# I2C_Bus.net
KiCad netlist of a schematic drawn in Altium Designer
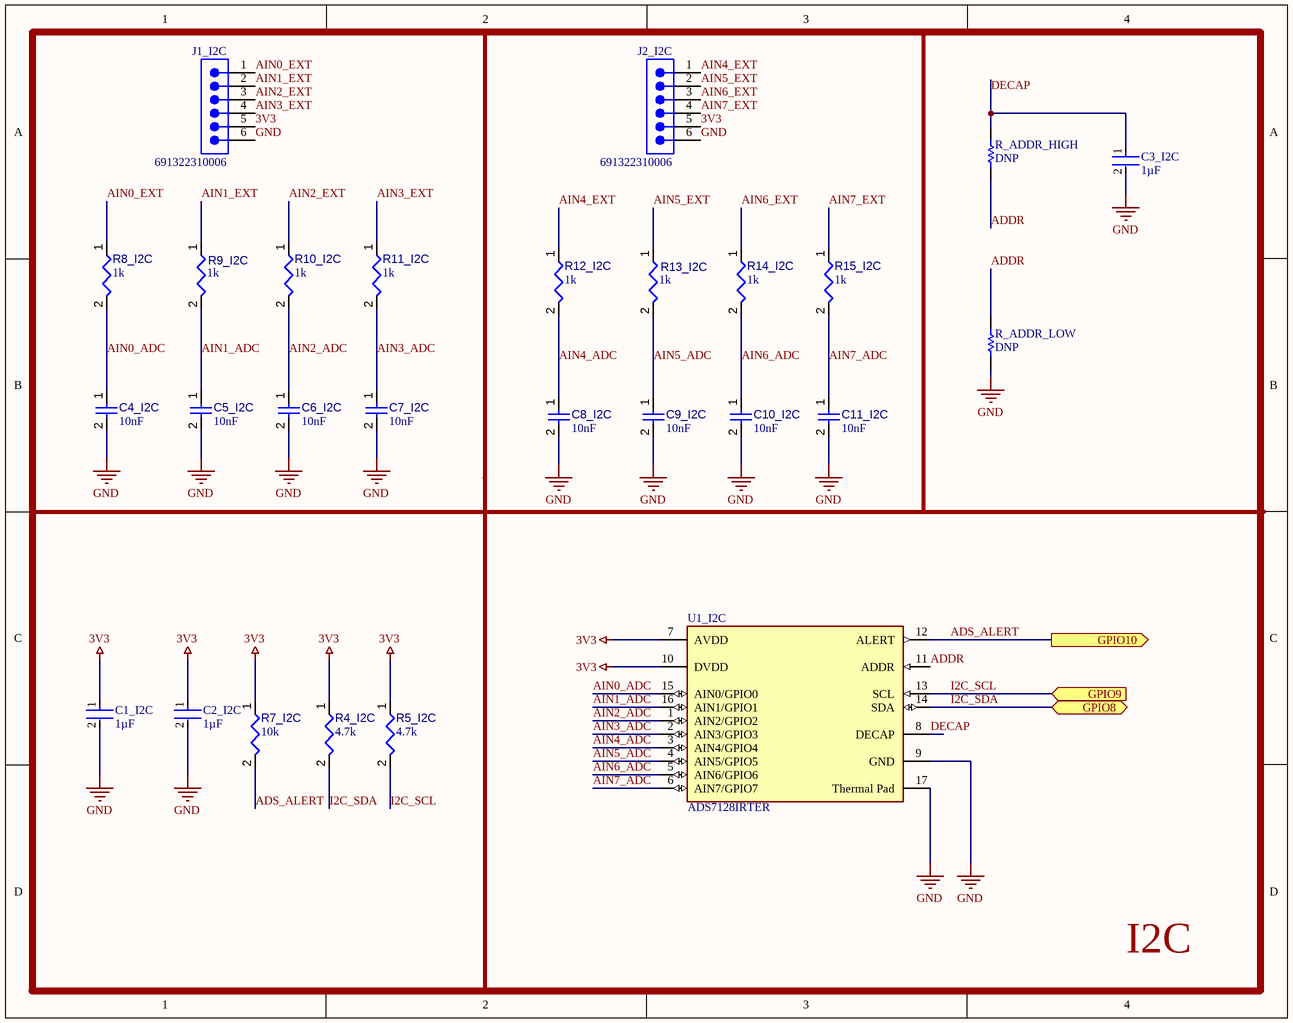
[diagram p0: I2C Bus.SchDoc]

(export (version "E")
  (design (tool "Eeschema 10.0.6"))
  (components
    (comp (ref "C1_I2C")
      (value "1µF")
      (footprint "FP-AC0805-0_85-IPC_A")
      (description "6.3V 1uF X7R ±10% 0805 Multilayer Ceramic Capacitors MLCC - SMD/SMT ROHS")
      (fields (field (name "TOLERANCE") "10%") (field (name "Comment") "AC0805KKX7R5BB105"))
      (libsource (lib "Faiz Agunda") (part "11868f565c42a9108669ba33697ecf6"))
    )
    (comp (ref "C2_I2C")
      (value "1µF")
      (footprint "FP-AC0805-0_85-IPC_A")
      (description "6.3V 1uF X7R ±10% 0805 Multilayer Ceramic Capacitors MLCC - SMD/SMT ROHS")
      (fields (field (name "TOLERANCE") "10%") (field (name "Comment") "AC0805KKX7R5BB105"))
      (libsource (lib "Faiz Agunda") (part "11868f565c42a9108669ba33697ecf6"))
    )
    (comp (ref "C3_I2C")
      (value "1µF")
      (footprint "FP-AC0805-0_85-IPC_A")
      (description "6.3V 1uF X7R ±10% 0805 Multilayer Ceramic Capacitors MLCC - SMD/SMT ROHS")
      (fields (field (name "TOLERANCE") "10%") (field (name "Comment") "AC0805KKX7R5BB105"))
      (libsource (lib "Faiz Agunda") (part "11868f565c42a9108669ba33697ecf6"))
    )
    (comp (ref "C4_I2C")
      (value "10nF")
      (footprint "CAPC0402(1005)60_L")
      (description "Chip Capacitor, 10nF +/-20%, 50V, 0402, Thickness 0.6 mm")
      (fields (field (name "TOLERANCE") "5%") (field (name "Comment") "Capacitor 10nF +/-20% 50V 0402"))
      (libsource (lib "Faiz Agunda") (part "CAP-NP-2"))
    )
    (comp (ref "C5_I2C")
      (value "10nF")
      (footprint "CAPC0402(1005)60_L")
      (description "Chip Capacitor, 10nF +/-20%, 50V, 0402, Thickness 0.6 mm")
      (fields (field (name "TOLERANCE") "5%") (field (name "Comment") "Capacitor 10nF +/-20% 50V 0402"))
      (libsource (lib "Faiz Agunda") (part "CAP-NP-2"))
    )
    (comp (ref "C6_I2C")
      (value "10nF")
      (footprint "CAPC0402(1005)60_L")
      (description "Chip Capacitor, 10nF +/-20%, 50V, 0402, Thickness 0.6 mm")
      (fields (field (name "TOLERANCE") "5%") (field (name "Comment") "Capacitor 10nF +/-20% 50V 0402"))
      (libsource (lib "Faiz Agunda") (part "CAP-NP-2"))
    )
    (comp (ref "C7_I2C")
      (value "10nF")
      (footprint "CAPC0402(1005)60_L")
      (description "Chip Capacitor, 10nF +/-20%, 50V, 0402, Thickness 0.6 mm")
      (fields (field (name "TOLERANCE") "5%") (field (name "Comment") "Capacitor 10nF +/-20% 50V 0402"))
      (libsource (lib "Faiz Agunda") (part "CAP-NP-2"))
    )
    (comp (ref "C8_I2C")
      (value "10nF")
      (footprint "CAPC0402(1005)60_L")
      (description "Chip Capacitor, 10nF +/-20%, 50V, 0402, Thickness 0.6 mm")
      (fields (field (name "TOLERANCE") "5%") (field (name "Comment") "Capacitor 10nF +/-20% 50V 0402"))
      (libsource (lib "Faiz Agunda") (part "CAP-NP-2"))
    )
    (comp (ref "C9_I2C")
      (value "10nF")
      (footprint "CAPC0402(1005)60_L")
      (description "Chip Capacitor, 10nF +/-20%, 50V, 0402, Thickness 0.6 mm")
      (fields (field (name "TOLERANCE") "5%") (field (name "Comment") "Capacitor 10nF +/-20% 50V 0402"))
      (libsource (lib "Faiz Agunda") (part "CAP-NP-2"))
    )
    (comp (ref "C10_I2C")
      (value "10nF")
      (footprint "CAPC0402(1005)60_L")
      (description "Chip Capacitor, 10nF +/-20%, 50V, 0402, Thickness 0.6 mm")
      (fields (field (name "TOLERANCE") "5%") (field (name "Comment") "Capacitor 10nF +/-20% 50V 0402"))
      (libsource (lib "Faiz Agunda") (part "CAP-NP-2"))
    )
    (comp (ref "C11_I2C")
      (value "10nF")
      (footprint "CAPC0402(1005)60_L")
      (description "Chip Capacitor, 10nF +/-20%, 50V, 0402, Thickness 0.6 mm")
      (fields (field (name "TOLERANCE") "5%") (field (name "Comment") "Capacitor 10nF +/-20% 50V 0402"))
      (libsource (lib "Faiz Agunda") (part "CAP-NP-2"))
    )
    (comp (ref "J1_I2C")
      (value "691322310006")
      (footprint "691322310006")
      (description "Wurth Elektronik 3.81mmpitch6pPlug-in terminal blocks socket head, 322series, 300.0 v, welding")
      (fields (field (name "VOLTAGE") "300V"))
      (libsource (lib "Faiz Agunda") (part "TBL - 1R - 06P - Male"))
    )
    (comp (ref "J2_I2C")
      (value "691322310006")
      (footprint "691322310006")
      (description "Wurth Elektronik 3.81mmpitch6pPlug-in terminal blocks socket head, 322series, 300.0 v, welding")
      (fields (field (name "VOLTAGE") "300V"))
      (libsource (lib "Faiz Agunda") (part "TBL - 1R - 06P - Male"))
    )
    (comp (ref "R4_I2C")
      (value "4.7k")
      (footprint "RESC1608X55X25ML10T15")
      (description "Chip Resistor, 4.7 KOhm, +/- 1%, 0.1 W, -55 to 155 degC, 0603 (1608 Metric)")
      (fields (field (name "TOLERANCE") "1%") (field (name "POWER") "100mW"))
      (libsource (lib "Faiz Agunda") (part "RES-2"))
    )
    (comp (ref "R5_I2C")
      (value "4.7k")
      (footprint "RESC1608X55X25ML10T15")
      (description "Chip Resistor, 4.7 KOhm, +/- 1%, 0.1 W, -55 to 155 degC, 0603 (1608 Metric)")
      (fields (field (name "TOLERANCE") "1%") (field (name "POWER") "100mW"))
      (libsource (lib "Faiz Agunda") (part "RES-2"))
    )
    (comp (ref "R7_I2C")
      (value "10k")
      (footprint "RESC0402(1005)_L")
      (description "Chip Resistor, 10 kOhms, +/-1 %, 63 mW, -55 to 125 degC, 0402")
      (fields (field (name "POWER") "63mW") (field (name "TOLERANCE") "1%"))
      (libsource (lib "Faiz Agunda") (part "RES-2"))
    )
    (comp (ref "R8_I2C")
      (value "1k")
      (footprint "RESC0805(2012)_L")
      (description "Chip Resistor, 1 kOhms, +/-5%, 125 mW, -55 to 155 degC, 0805")
      (fields (field (name "TOLERANCE") "5%") (field (name "POWER") "125mW"))
      (libsource (lib "Faiz Agunda") (part "RES-2"))
    )
    (comp (ref "R9_I2C")
      (value "1k")
      (footprint "RESC0805(2012)_L")
      (description "Chip Resistor, 1 kOhms, +/-5%, 125 mW, -55 to 155 degC, 0805")
      (fields (field (name "TOLERANCE") "5%") (field (name "POWER") "125mW"))
      (libsource (lib "Faiz Agunda") (part "RES-2"))
    )
    (comp (ref "R10_I2C")
      (value "1k")
      (footprint "RESC0805(2012)_L")
      (description "Chip Resistor, 1 kOhms, +/-5%, 125 mW, -55 to 155 degC, 0805")
      (fields (field (name "TOLERANCE") "5%") (field (name "POWER") "125mW"))
      (libsource (lib "Faiz Agunda") (part "RES-2"))
    )
    (comp (ref "R11_I2C")
      (value "1k")
      (footprint "RESC0805(2012)_L")
      (description "Chip Resistor, 1 kOhms, +/-5%, 125 mW, -55 to 155 degC, 0805")
      (fields (field (name "TOLERANCE") "5%") (field (name "POWER") "125mW"))
      (libsource (lib "Faiz Agunda") (part "RES-2"))
    )
    (comp (ref "R12_I2C")
      (value "1k")
      (footprint "RESC0805(2012)_L")
      (description "Chip Resistor, 1 kOhms, +/-5%, 125 mW, -55 to 155 degC, 0805")
      (fields (field (name "TOLERANCE") "5%") (field (name "POWER") "125mW"))
      (libsource (lib "Faiz Agunda") (part "RES-2"))
    )
    (comp (ref "R13_I2C")
      (value "1k")
      (footprint "RESC0805(2012)_L")
      (description "Chip Resistor, 1 kOhms, +/-5%, 125 mW, -55 to 155 degC, 0805")
      (fields (field (name "TOLERANCE") "5%") (field (name "POWER") "125mW"))
      (libsource (lib "Faiz Agunda") (part "RES-2"))
    )
    (comp (ref "R14_I2C")
      (value "1k")
      (footprint "RESC0805(2012)_L")
      (description "Chip Resistor, 1 kOhms, +/-5%, 125 mW, -55 to 155 degC, 0805")
      (fields (field (name "TOLERANCE") "5%") (field (name "POWER") "125mW"))
      (libsource (lib "Faiz Agunda") (part "RES-2"))
    )
    (comp (ref "R15_I2C")
      (value "1k")
      (footprint "RESC0805(2012)_L")
      (description "Chip Resistor, 1 kOhms, +/-5%, 125 mW, -55 to 155 degC, 0805")
      (fields (field (name "TOLERANCE") "5%") (field (name "POWER") "125mW"))
      (libsource (lib "Faiz Agunda") (part "RES-2"))
    )
    (comp (ref "R_ADDR_HIGH")
      (value "DNP")
      (footprint "RESC1005X40X25ML05T05")
      (description "Chip Resistor, 0 Ohm, 0.1 W, -55 to 155 degC, 0402 (1005 Metric)")
      (fields (field (name "TOLERANCE") "5%") (field (name "POWER") "100mW"))
      (libsource (lib "") (part "RES-2_1"))
    )
    (comp (ref "R_ADDR_LOW")
      (value "DNP")
      (footprint "RESC1005X40X25ML05T05")
      (description "Chip Resistor, 0 Ohm, 0.1 W, -55 to 155 degC, 0402 (1005 Metric)")
      (fields (field (name "TOLERANCE") "5%") (field (name "POWER") "100mW"))
      (libsource (lib "") (part "RES-2_1"))
    )
    (comp (ref "U1_I2C")
      (value "ADS7128IRTER")
      (footprint "FP-RTE0016C-IPC_B")
      (description "IC ADC 12BIT SAR 16WQFN / 12 Bit Analog to Digital Converter 8 Input 1 SAR 16-WQFN (3x3)")
      (libsource (lib "Faiz Agunda") (part "2119cd08cb31c72c493aed5ff76a044"))
    )
  )
  (nets
    (net (code "2") (name "/ADDR") (class "Default")
      (node (ref "R_ADDR_HIGH") (pin "1") (pinfunction "1_1") (pintype "passive"))
      (node (ref "R_ADDR_LOW") (pin "2") (pinfunction "2_2") (pintype "passive"))
      (node (ref "U1_I2C") (pin "11") (pinfunction "ADDR_11") (pintype "input"))
    )
    (net (code "3") (name "/ADS_ALERT") (class "Default")
      (node (ref "R7_I2C") (pin "2") (pinfunction "2_2") (pintype "passive"))
      (node (ref "U1_I2C") (pin "12") (pinfunction "ALERT_12") (pintype "output"))
    )
    (net (code "4") (name "/AIN0_ADC") (class "Default")
      (node (ref "C4_I2C") (pin "1") (pinfunction "1_1") (pintype "passive"))
      (node (ref "R8_I2C") (pin "2") (pinfunction "2_2") (pintype "passive"))
      (node (ref "U1_I2C") (pin "15") (pinfunction "AIN0/GPIO0_15") (pintype "bidirectional"))
    )
    (net (code "5") (name "/AIN0_EXT") (class "Default")
      (node (ref "J1_I2C") (pin "1") (pinfunction "1_1") (pintype "passive"))
      (node (ref "R8_I2C") (pin "1") (pinfunction "1_1") (pintype "passive"))
    )
    (net (code "6") (name "/AIN1_ADC") (class "Default")
      (node (ref "C5_I2C") (pin "1") (pinfunction "1_1") (pintype "passive"))
      (node (ref "R9_I2C") (pin "2") (pinfunction "2_2") (pintype "passive"))
      (node (ref "U1_I2C") (pin "16") (pinfunction "AIN1/GPIO1_16") (pintype "bidirectional"))
    )
    (net (code "7") (name "/AIN1_EXT") (class "Default")
      (node (ref "J1_I2C") (pin "2") (pinfunction "2_2") (pintype "passive"))
      (node (ref "R9_I2C") (pin "1") (pinfunction "1_1") (pintype "passive"))
    )
    (net (code "8") (name "/AIN2_ADC") (class "Default")
      (node (ref "C6_I2C") (pin "1") (pinfunction "1_1") (pintype "passive"))
      (node (ref "R10_I2C") (pin "2") (pinfunction "2_2") (pintype "passive"))
      (node (ref "U1_I2C") (pin "1") (pinfunction "AIN2/GPIO2_1") (pintype "bidirectional"))
    )
    (net (code "9") (name "/AIN2_EXT") (class "Default")
      (node (ref "J1_I2C") (pin "3") (pinfunction "3_3") (pintype "passive"))
      (node (ref "R10_I2C") (pin "1") (pinfunction "1_1") (pintype "passive"))
    )
    (net (code "10") (name "/AIN3_ADC") (class "Default")
      (node (ref "C7_I2C") (pin "1") (pinfunction "1_1") (pintype "passive"))
      (node (ref "R11_I2C") (pin "2") (pinfunction "2_2") (pintype "passive"))
      (node (ref "U1_I2C") (pin "2") (pinfunction "AIN3/GPIO3_2") (pintype "bidirectional"))
    )
    (net (code "11") (name "/AIN3_EXT") (class "Default")
      (node (ref "J1_I2C") (pin "4") (pinfunction "4_4") (pintype "passive"))
      (node (ref "R11_I2C") (pin "1") (pinfunction "1_1") (pintype "passive"))
    )
    (net (code "12") (name "/AIN4_ADC") (class "Default")
      (node (ref "C8_I2C") (pin "1") (pinfunction "1_1") (pintype "passive"))
      (node (ref "R12_I2C") (pin "2") (pinfunction "2_2") (pintype "passive"))
      (node (ref "U1_I2C") (pin "3") (pinfunction "AIN4/GPIO4_3") (pintype "bidirectional"))
    )
    (net (code "13") (name "/AIN4_EXT") (class "Default")
      (node (ref "J2_I2C") (pin "1") (pinfunction "1_1") (pintype "passive"))
      (node (ref "R12_I2C") (pin "1") (pinfunction "1_1") (pintype "passive"))
    )
    (net (code "14") (name "/AIN5_ADC") (class "Default")
      (node (ref "C9_I2C") (pin "1") (pinfunction "1_1") (pintype "passive"))
      (node (ref "R13_I2C") (pin "2") (pinfunction "2_2") (pintype "passive"))
      (node (ref "U1_I2C") (pin "4") (pinfunction "AIN5/GPIO5_4") (pintype "bidirectional"))
    )
    (net (code "15") (name "/AIN5_EXT") (class "Default")
      (node (ref "J2_I2C") (pin "2") (pinfunction "2_2") (pintype "passive"))
      (node (ref "R13_I2C") (pin "1") (pinfunction "1_1") (pintype "passive"))
    )
    (net (code "16") (name "/AIN6_ADC") (class "Default")
      (node (ref "C10_I2C") (pin "1") (pinfunction "1_1") (pintype "passive"))
      (node (ref "R14_I2C") (pin "2") (pinfunction "2_2") (pintype "passive"))
      (node (ref "U1_I2C") (pin "5") (pinfunction "AIN6/GPIO6_5") (pintype "bidirectional"))
    )
    (net (code "17") (name "/AIN6_EXT") (class "Default")
      (node (ref "J2_I2C") (pin "3") (pinfunction "3_3") (pintype "passive"))
      (node (ref "R14_I2C") (pin "1") (pinfunction "1_1") (pintype "passive"))
    )
    (net (code "18") (name "/AIN7_ADC") (class "Default")
      (node (ref "C11_I2C") (pin "1") (pinfunction "1_1") (pintype "passive"))
      (node (ref "R15_I2C") (pin "2") (pinfunction "2_2") (pintype "passive"))
      (node (ref "U1_I2C") (pin "6") (pinfunction "AIN7/GPIO7_6") (pintype "bidirectional"))
    )
    (net (code "19") (name "/AIN7_EXT") (class "Default")
      (node (ref "J2_I2C") (pin "4") (pinfunction "4_4") (pintype "passive"))
      (node (ref "R15_I2C") (pin "1") (pinfunction "1_1") (pintype "passive"))
    )
    (net (code "20") (name "/DECAP") (class "Default")
      (node (ref "C3_I2C") (pin "1") (pinfunction "1_1") (pintype "passive"))
      (node (ref "R_ADDR_HIGH") (pin "2") (pinfunction "2_2") (pintype "passive"))
      (node (ref "U1_I2C") (pin "8") (pinfunction "DECAP_8") (pintype "power_in"))
    )
    (net (code "21") (name "/I2C_SCL") (class "Default")
      (node (ref "R5_I2C") (pin "2") (pinfunction "2_2") (pintype "passive"))
      (node (ref "U1_I2C") (pin "13") (pinfunction "SCL_13") (pintype "input"))
    )
    (net (code "22") (name "/I2C_SDA") (class "Default")
      (node (ref "R4_I2C") (pin "2") (pinfunction "2_2") (pintype "passive"))
      (node (ref "U1_I2C") (pin "14") (pinfunction "SDA_14") (pintype "bidirectional"))
    )
    (net (code "23") (name "3V3") (class "Default")
      (node (ref "C1_I2C") (pin "1") (pinfunction "1_1") (pintype "passive"))
      (node (ref "C2_I2C") (pin "1") (pinfunction "1_1") (pintype "passive"))
      (node (ref "J1_I2C") (pin "5") (pinfunction "5_5") (pintype "passive"))
      (node (ref "J2_I2C") (pin "5") (pinfunction "5_5") (pintype "passive"))
      (node (ref "R4_I2C") (pin "1") (pinfunction "1_1") (pintype "passive"))
      (node (ref "R5_I2C") (pin "1") (pinfunction "1_1") (pintype "passive"))
      (node (ref "R7_I2C") (pin "1") (pinfunction "1_1") (pintype "passive"))
      (node (ref "U1_I2C") (pin "10") (pinfunction "DVDD_10") (pintype "power_in"))
      (node (ref "U1_I2C") (pin "7") (pinfunction "AVDD_7") (pintype "power_in"))
    )
    (net (code "24") (name "GND") (class "Default")
      (node (ref "C10_I2C") (pin "2") (pinfunction "2_2") (pintype "passive"))
      (node (ref "C11_I2C") (pin "2") (pinfunction "2_2") (pintype "passive"))
      (node (ref "C1_I2C") (pin "2") (pinfunction "2_2") (pintype "passive"))
      (node (ref "C2_I2C") (pin "2") (pinfunction "2_2") (pintype "passive"))
      (node (ref "C3_I2C") (pin "2") (pinfunction "2_2") (pintype "passive"))
      (node (ref "C4_I2C") (pin "2") (pinfunction "2_2") (pintype "passive"))
      (node (ref "C5_I2C") (pin "2") (pinfunction "2_2") (pintype "passive"))
      (node (ref "C6_I2C") (pin "2") (pinfunction "2_2") (pintype "passive"))
      (node (ref "C7_I2C") (pin "2") (pinfunction "2_2") (pintype "passive"))
      (node (ref "C8_I2C") (pin "2") (pinfunction "2_2") (pintype "passive"))
      (node (ref "C9_I2C") (pin "2") (pinfunction "2_2") (pintype "passive"))
      (node (ref "J1_I2C") (pin "6") (pinfunction "6_6") (pintype "passive"))
      (node (ref "J2_I2C") (pin "6") (pinfunction "6_6") (pintype "passive"))
      (node (ref "R_ADDR_LOW") (pin "1") (pinfunction "1_1") (pintype "passive"))
      (node (ref "U1_I2C") (pin "17") (pinfunction "Thermal_Pad_17") (pintype "power_in"))
      (node (ref "U1_I2C") (pin "9") (pinfunction "GND_9") (pintype "power_in"))
    )
  )
)
